# elec.net
KiCad netlist of a schematic drawn in Altium Designer
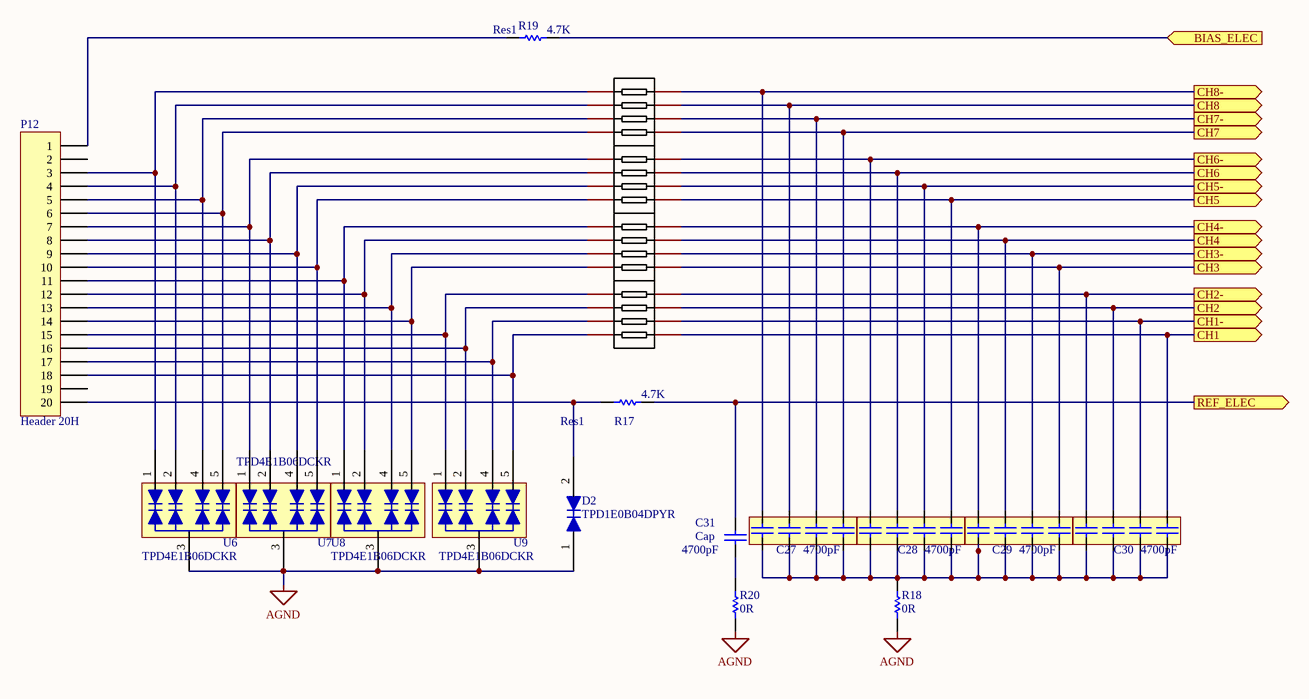
[diagram p0: elec.SchDoc]

(export (version "E")
  (design (tool "Eeschema 10.0.6"))
  (components
    (comp (ref "C27")
      (value "50V")
      (footprint "1206C-ARRAY")
      (description "CAP .1UF 50V CERAMIC Y5V 0805")
      (fields
        (field (name "MANUFACTURER") "TDK")
        (field (name "PCN PART NUMBER") "MLCC Part Number Change 30/Nov/2012")
        (field (name "CAPACITANCE") "4700pF")
      )
      (libsource (lib "LUCHADOR SCHLIB") (part "Cap"))
    )
    (comp (ref "C28")
      (value "50V")
      (footprint "1206C-ARRAY")
      (description "CAP .1UF 50V CERAMIC Y5V 0805")
      (fields
        (field (name "MANUFACTURER") "TDK")
        (field (name "PCN PART NUMBER") "MLCC Part Number Change 30/Nov/2012")
        (field (name "CAPACITANCE") "4700pF")
      )
      (libsource (lib "LUCHADOR SCHLIB") (part "Cap"))
    )
    (comp (ref "C29")
      (value "50V")
      (footprint "1206C-ARRAY")
      (description "CAP .1UF 50V CERAMIC Y5V 0805")
      (fields
        (field (name "MANUFACTURER") "TDK")
        (field (name "PCN PART NUMBER") "MLCC Part Number Change 30/Nov/2012")
        (field (name "CAPACITANCE") "4700pF")
      )
      (libsource (lib "LUCHADOR SCHLIB") (part "Cap"))
    )
    (comp (ref "C30")
      (value "50V")
      (footprint "1206C-ARRAY")
      (description "CAP .1UF 50V CERAMIC Y5V 0805")
      (fields
        (field (name "MANUFACTURER") "TDK")
        (field (name "PCN PART NUMBER") "MLCC Part Number Change 30/Nov/2012")
        (field (name "CAPACITANCE") "4700pF")
      )
      (libsource (lib "LUCHADOR SCHLIB") (part "Cap"))
    )
    (comp (ref "C31")
      (value "Cap")
      (footprint "0402C")
      (description "Capacitor")
      (fields (field (name "ALTIUM_VALUE") "4700pF") (field (name "PUBLISHER") "Altium Limited"))
      (libsource (lib "Miscellaneous Devices") (part "Cap"))
    )
    (comp (ref "D2")
      (value "TPD1E0B04DPYR")
      (footprint "0402D")
      (fields
        (field (name "MANUFACTURER") "Texas Instruments")
        (field (name "MANUFACTURER PART NUMBER") "TPD1E0B04DPYR")
      )
      (libsource (lib "LUCHADOR SCHLIB") (part "TPD1E0B04DPYR"))
    )
    (comp (ref "P12")
      (value "Header 20H")
      (footprint "HDR1X20H")
      (description "Header, 20-Pin, Right Angle")
      (fields (field (name "PUBLISHER") "Altium Limited"))
      (libsource (lib "Miscellaneous Connectors") (part "Header 20H"))
    )
    (comp (ref "R17")
      (value "Res1")
      (footprint "0603")
      (description "Resistor")
      (fields (field (name "ALTIUM_VALUE") "4.7K") (field (name "PUBLISHER") "Altium Limited"))
      (libsource (lib "Miscellaneous Devices") (part "Res1"))
    )
    (comp (ref "R18")
      (value "Res 0805")
      (footprint "0603")
      (description "Resistor")
      (fields
        (field (name "MANUFACTURER") "Panasonic")
        (field (name "MANUFACTURER PART NUMBER") "ERJ-2GE0R00X")
        (field (name "RESISTANCE (OHMS)") "0R")
      )
      (libsource (lib "RAPTOR MCB SCHLIB") (part "Res 0805"))
    )
    (comp (ref "R19")
      (value "Res1")
      (footprint "0603")
      (description "Resistor")
      (fields (field (name "ALTIUM_VALUE") "4.7K") (field (name "PUBLISHER") "Altium Limited"))
      (libsource (lib "Miscellaneous Devices") (part "Res1"))
    )
    (comp (ref "R20")
      (value "Res 0805")
      (footprint "0603")
      (description "Resistor")
      (fields
        (field (name "MANUFACTURER") "Panasonic")
        (field (name "MANUFACTURER PART NUMBER") "ERJ-2GE0R00X")
        (field (name "RESISTANCE (OHMS)") "0R")
      )
      (libsource (lib "RAPTOR MCB SCHLIB") (part "Res 0805"))
    )
    (comp (ref "RA1")
      (value "4D03WGF4701T5E")
      (footprint "RES-ARRAY-SMD_0603-8P-L3.2-W1.6-BL")
      (fields (field (name "MANUFACTURER") "UNI-ROYAL(厚声)") (field (name "TOLERANCE") "±1%"))
      (libsource (lib "4D03WGF4701T5E1_4D03WGF4701T5E.schdoc") (part "4D03WGF4701T5E"))
    )
    (comp (ref "RA2")
      (value "4D03WGF4701T5E")
      (footprint "RES-ARRAY-SMD_0603-8P-L3.2-W1.6-BL")
      (fields (field (name "MANUFACTURER") "UNI-ROYAL(厚声)") (field (name "TOLERANCE") "±1%"))
      (libsource (lib "4D03WGF4701T5E1_4D03WGF4701T5E.schdoc") (part "4D03WGF4701T5E"))
    )
    (comp (ref "RA3")
      (value "4D03WGF4701T5E")
      (footprint "RES-ARRAY-SMD_0603-8P-L3.2-W1.6-BL")
      (fields (field (name "MANUFACTURER") "UNI-ROYAL(厚声)") (field (name "TOLERANCE") "±1%"))
      (libsource (lib "4D03WGF4701T5E1_4D03WGF4701T5E.schdoc") (part "4D03WGF4701T5E"))
    )
    (comp (ref "RA4")
      (value "4D03WGF4701T5E")
      (footprint "RES-ARRAY-SMD_0603-8P-L3.2-W1.6-BL")
      (fields (field (name "MANUFACTURER") "UNI-ROYAL(厚声)") (field (name "TOLERANCE") "±1%"))
      (libsource (lib "4D03WGF4701T5E1_4D03WGF4701T5E.schdoc") (part "4D03WGF4701T5E"))
    )
    (comp (ref "U6")
      (value "TPD4E1B06DCKR")
      (footprint "DCK6_TEX")
      (fields
        (field (name "MANUFACTURER") "Texas Instruments")
        (field (name "MANUFACTURER PART NUMBER") "TPD4E1B06DCKR")
      )
      (libsource (lib "LUCHADOR SCHLIB") (part "TPD4E1B06DCKR"))
    )
    (comp (ref "U7")
      (value "TPD4E1B06DCKR")
      (footprint "DCK6_TEX")
      (fields
        (field (name "MANUFACTURER") "Texas Instruments")
        (field (name "MANUFACTURER PART NUMBER") "TPD4E1B06DCKR")
      )
      (libsource (lib "LUCHADOR SCHLIB") (part "TPD4E1B06DCKR"))
    )
    (comp (ref "U8")
      (value "TPD4E1B06DCKR")
      (footprint "DCK6_TEX")
      (fields
        (field (name "MANUFACTURER") "Texas Instruments")
        (field (name "MANUFACTURER PART NUMBER") "TPD4E1B06DCKR")
      )
      (libsource (lib "LUCHADOR SCHLIB") (part "TPD4E1B06DCKR"))
    )
    (comp (ref "U9")
      (value "TPD4E1B06DCKR")
      (footprint "DCK6_TEX")
      (fields
        (field (name "MANUFACTURER") "Texas Instruments")
        (field (name "MANUFACTURER PART NUMBER") "TPD4E1B06DCKR")
      )
      (libsource (lib "LUCHADOR SCHLIB") (part "TPD4E1B06DCKR"))
    )
  )
  (nets
    (net (code "1") (name "/BIAS_ELEC") (class "Default")
      (node (ref "R19") (pin "2") (pinfunction "2_2") (pintype "passive"))
    )
    (net (code "2") (name "/CH1") (class "Default")
      (node (ref "C30") (pin "A4") (pinfunction "A4_A4") (pintype "passive"))
      (node (ref "RA4") (pin "5") (pinfunction "5_5") (pintype "passive"))
    )
    (net (code "3") (name "/CH1-") (class "Default")
      (node (ref "C30") (pin "A3") (pinfunction "A3_A3") (pintype "passive"))
      (node (ref "RA4") (pin "6") (pinfunction "6_6") (pintype "passive"))
    )
    (net (code "4") (name "/CH2") (class "Default")
      (node (ref "C30") (pin "A2") (pinfunction "A2_A2") (pintype "passive"))
      (node (ref "RA4") (pin "7") (pinfunction "7_7") (pintype "passive"))
    )
    (net (code "5") (name "/CH2-") (class "Default")
      (node (ref "C30") (pin "A1") (pinfunction "A1_A1") (pintype "passive"))
      (node (ref "RA4") (pin "8") (pinfunction "8_8") (pintype "passive"))
    )
    (net (code "6") (name "/CH3") (class "Default")
      (node (ref "C29") (pin "A4") (pinfunction "A4_A4") (pintype "passive"))
      (node (ref "RA3") (pin "5") (pinfunction "5_5") (pintype "passive"))
    )
    (net (code "7") (name "/CH3-") (class "Default")
      (node (ref "C29") (pin "A3") (pinfunction "A3_A3") (pintype "passive"))
      (node (ref "RA3") (pin "6") (pinfunction "6_6") (pintype "passive"))
    )
    (net (code "8") (name "/CH4") (class "Default")
      (node (ref "C29") (pin "A2") (pinfunction "A2_A2") (pintype "passive"))
      (node (ref "RA3") (pin "7") (pinfunction "7_7") (pintype "passive"))
    )
    (net (code "9") (name "/CH4-") (class "Default")
      (node (ref "C29") (pin "A1") (pinfunction "A1_A1") (pintype "passive"))
      (node (ref "RA3") (pin "8") (pinfunction "8_8") (pintype "passive"))
    )
    (net (code "10") (name "/CH5") (class "Default")
      (node (ref "C28") (pin "A4") (pinfunction "A4_A4") (pintype "passive"))
      (node (ref "RA2") (pin "5") (pinfunction "5_5") (pintype "passive"))
    )
    (net (code "11") (name "/CH5-") (class "Default")
      (node (ref "C28") (pin "A3") (pinfunction "A3_A3") (pintype "passive"))
      (node (ref "RA2") (pin "6") (pinfunction "6_6") (pintype "passive"))
    )
    (net (code "12") (name "/CH6") (class "Default")
      (node (ref "C28") (pin "A2") (pinfunction "A2_A2") (pintype "passive"))
      (node (ref "RA2") (pin "7") (pinfunction "7_7") (pintype "passive"))
    )
    (net (code "13") (name "/CH6-") (class "Default")
      (node (ref "C28") (pin "A1") (pinfunction "A1_A1") (pintype "passive"))
      (node (ref "RA2") (pin "8") (pinfunction "8_8") (pintype "passive"))
    )
    (net (code "14") (name "/CH7") (class "Default")
      (node (ref "C27") (pin "A4") (pinfunction "A4_A4") (pintype "passive"))
      (node (ref "RA1") (pin "5") (pinfunction "5_5") (pintype "passive"))
    )
    (net (code "15") (name "/CH7-") (class "Default")
      (node (ref "C27") (pin "A3") (pinfunction "A3_A3") (pintype "passive"))
      (node (ref "RA1") (pin "6") (pinfunction "6_6") (pintype "passive"))
    )
    (net (code "16") (name "/CH8") (class "Default")
      (node (ref "C27") (pin "A2") (pinfunction "A2_A2") (pintype "passive"))
      (node (ref "RA1") (pin "7") (pinfunction "7_7") (pintype "passive"))
    )
    (net (code "17") (name "/CH8-") (class "Default")
      (node (ref "C27") (pin "A1") (pinfunction "A1_A1") (pintype "passive"))
      (node (ref "RA1") (pin "8") (pinfunction "8_8") (pintype "passive"))
    )
    (net (code "18") (name "/REF_ELEC") (class "Default")
      (node (ref "C31") (pin "2") (pinfunction "2_2") (pintype "passive"))
      (node (ref "R17") (pin "2") (pinfunction "2_2") (pintype "passive"))
    )
    (net (code "19") (name "AGND") (class "Default")
      (node (ref "D2") (pin "1") (pinfunction "IO1_1") (pintype "passive"))
      (node (ref "R18") (pin "1") (pinfunction "1_1") (pintype "passive"))
      (node (ref "R20") (pin "1") (pinfunction "1_1") (pintype "passive"))
      (node (ref "U6") (pin "3") (pinfunction "GND_3") (pintype "passive"))
      (node (ref "U7") (pin "3") (pinfunction "GND_3") (pintype "passive"))
      (node (ref "U8") (pin "3") (pinfunction "GND_3") (pintype "passive"))
      (node (ref "U9") (pin "3") (pinfunction "GND_3") (pintype "passive"))
    )
    (net (code "20") (name "Net-(C27-PadB1)") (class "Default")
      (node (ref "C27") (pin "B1") (pinfunction "B1_B1") (pintype "passive"))
      (node (ref "C27") (pin "B2") (pinfunction "B2_B2") (pintype "passive"))
      (node (ref "C27") (pin "B3") (pinfunction "B3_B3") (pintype "passive"))
      (node (ref "C27") (pin "B4") (pinfunction "B4_B4") (pintype "passive"))
      (node (ref "C28") (pin "B1") (pinfunction "B1_B1") (pintype "passive"))
      (node (ref "C28") (pin "B2") (pinfunction "B2_B2") (pintype "passive"))
      (node (ref "C28") (pin "B3") (pinfunction "B3_B3") (pintype "passive"))
      (node (ref "C28") (pin "B4") (pinfunction "B4_B4") (pintype "passive"))
      (node (ref "C29") (pin "B1") (pinfunction "B1_B1") (pintype "passive"))
      (node (ref "C29") (pin "B2") (pinfunction "B2_B2") (pintype "passive"))
      (node (ref "C29") (pin "B3") (pinfunction "B3_B3") (pintype "passive"))
      (node (ref "C29") (pin "B4") (pinfunction "B4_B4") (pintype "passive"))
      (node (ref "C30") (pin "B1") (pinfunction "B1_B1") (pintype "passive"))
      (node (ref "C30") (pin "B2") (pinfunction "B2_B2") (pintype "passive"))
      (node (ref "C30") (pin "B3") (pinfunction "B3_B3") (pintype "passive"))
      (node (ref "C30") (pin "B4") (pinfunction "B4_B4") (pintype "passive"))
      (node (ref "R18") (pin "2") (pinfunction "2_2") (pintype "passive"))
    )
    (net (code "21") (name "Net-(C31-Pad1)") (class "Default")
      (node (ref "C31") (pin "1") (pinfunction "1_1") (pintype "passive"))
      (node (ref "R20") (pin "2") (pinfunction "2_2") (pintype "passive"))
    )
    (net (code "22") (name "Net-(D2-GND)") (class "Default")
      (node (ref "D2") (pin "2") (pinfunction "GND_2") (pintype "passive"))
      (node (ref "P12") (pin "20") (pinfunction "20_20") (pintype "passive"))
      (node (ref "R17") (pin "1") (pinfunction "1_1") (pintype "passive"))
    )
    (net (code "23") (name "Net-(P12-Pad1)") (class "Default")
      (node (ref "P12") (pin "1") (pinfunction "1_1") (pintype "passive"))
      (node (ref "R19") (pin "1") (pinfunction "1_1") (pintype "passive"))
    )
    (net (code "24") (name "Net-(U6-IO1)") (class "Default")
      (node (ref "P12") (pin "3") (pinfunction "3_3") (pintype "passive"))
      (node (ref "RA1") (pin "1") (pinfunction "1_1") (pintype "passive"))
      (node (ref "U6") (pin "1") (pinfunction "IO1_1") (pintype "passive"))
    )
    (net (code "25") (name "Net-(U6-IO2)") (class "Default")
      (node (ref "P12") (pin "4") (pinfunction "4_4") (pintype "passive"))
      (node (ref "RA1") (pin "2") (pinfunction "2_2") (pintype "passive"))
      (node (ref "U6") (pin "2") (pinfunction "IO2_2") (pintype "passive"))
    )
    (net (code "26") (name "Net-(U6-IO3)") (class "Default")
      (node (ref "P12") (pin "5") (pinfunction "5_5") (pintype "passive"))
      (node (ref "RA1") (pin "3") (pinfunction "3_3") (pintype "passive"))
      (node (ref "U6") (pin "4") (pinfunction "IO3_4") (pintype "passive"))
    )
    (net (code "27") (name "Net-(U6-IO4)") (class "Default")
      (node (ref "P12") (pin "6") (pinfunction "6_6") (pintype "passive"))
      (node (ref "RA1") (pin "4") (pinfunction "4_4") (pintype "passive"))
      (node (ref "U6") (pin "5") (pinfunction "IO4_5") (pintype "passive"))
    )
    (net (code "28") (name "Net-(U7-IO1)") (class "Default")
      (node (ref "P12") (pin "7") (pinfunction "7_7") (pintype "passive"))
      (node (ref "RA2") (pin "1") (pinfunction "1_1") (pintype "passive"))
      (node (ref "U7") (pin "1") (pinfunction "IO1_1") (pintype "passive"))
    )
    (net (code "29") (name "Net-(U7-IO2)") (class "Default")
      (node (ref "P12") (pin "8") (pinfunction "8_8") (pintype "passive"))
      (node (ref "RA2") (pin "2") (pinfunction "2_2") (pintype "passive"))
      (node (ref "U7") (pin "2") (pinfunction "IO2_2") (pintype "passive"))
    )
    (net (code "30") (name "Net-(U7-IO3)") (class "Default")
      (node (ref "P12") (pin "9") (pinfunction "9_9") (pintype "passive"))
      (node (ref "RA2") (pin "3") (pinfunction "3_3") (pintype "passive"))
      (node (ref "U7") (pin "4") (pinfunction "IO3_4") (pintype "passive"))
    )
    (net (code "31") (name "Net-(U7-IO4)") (class "Default")
      (node (ref "P12") (pin "10") (pinfunction "10_10") (pintype "passive"))
      (node (ref "RA2") (pin "4") (pinfunction "4_4") (pintype "passive"))
      (node (ref "U7") (pin "5") (pinfunction "IO4_5") (pintype "passive"))
    )
    (net (code "32") (name "Net-(U8-IO1)") (class "Default")
      (node (ref "P12") (pin "11") (pinfunction "11_11") (pintype "passive"))
      (node (ref "RA3") (pin "1") (pinfunction "1_1") (pintype "passive"))
      (node (ref "U8") (pin "1") (pinfunction "IO1_1") (pintype "passive"))
    )
    (net (code "33") (name "Net-(U8-IO2)") (class "Default")
      (node (ref "P12") (pin "12") (pinfunction "12_12") (pintype "passive"))
      (node (ref "RA3") (pin "2") (pinfunction "2_2") (pintype "passive"))
      (node (ref "U8") (pin "2") (pinfunction "IO2_2") (pintype "passive"))
    )
    (net (code "34") (name "Net-(U8-IO3)") (class "Default")
      (node (ref "P12") (pin "13") (pinfunction "13_13") (pintype "passive"))
      (node (ref "RA3") (pin "3") (pinfunction "3_3") (pintype "passive"))
      (node (ref "U8") (pin "4") (pinfunction "IO3_4") (pintype "passive"))
    )
    (net (code "35") (name "Net-(U8-IO4)") (class "Default")
      (node (ref "P12") (pin "14") (pinfunction "14_14") (pintype "passive"))
      (node (ref "RA3") (pin "4") (pinfunction "4_4") (pintype "passive"))
      (node (ref "U8") (pin "5") (pinfunction "IO4_5") (pintype "passive"))
    )
    (net (code "36") (name "Net-(U9-IO1)") (class "Default")
      (node (ref "P12") (pin "15") (pinfunction "15_15") (pintype "passive"))
      (node (ref "RA4") (pin "1") (pinfunction "1_1") (pintype "passive"))
      (node (ref "U9") (pin "1") (pinfunction "IO1_1") (pintype "passive"))
    )
    (net (code "37") (name "Net-(U9-IO2)") (class "Default")
      (node (ref "P12") (pin "16") (pinfunction "16_16") (pintype "passive"))
      (node (ref "RA4") (pin "2") (pinfunction "2_2") (pintype "passive"))
      (node (ref "U9") (pin "2") (pinfunction "IO2_2") (pintype "passive"))
    )
    (net (code "38") (name "Net-(U9-IO3)") (class "Default")
      (node (ref "P12") (pin "17") (pinfunction "17_17") (pintype "passive"))
      (node (ref "RA4") (pin "3") (pinfunction "3_3") (pintype "passive"))
      (node (ref "U9") (pin "4") (pinfunction "IO3_4") (pintype "passive"))
    )
    (net (code "39") (name "Net-(U9-IO4)") (class "Default")
      (node (ref "P12") (pin "18") (pinfunction "18_18") (pintype "passive"))
      (node (ref "RA4") (pin "4") (pinfunction "4_4") (pintype "passive"))
      (node (ref "U9") (pin "5") (pinfunction "IO4_5") (pintype "passive"))
    )
    (net (code "40") (name "unconnected-(P12-Pad2)") (class "Default")
      (node (ref "P12") (pin "2") (pinfunction "2_2") (pintype "passive"))
    )
    (net (code "41") (name "unconnected-(P12-Pad19)") (class "Default")
      (node (ref "P12") (pin "19") (pinfunction "19_19") (pintype "passive"))
    )
  )
)
